# ReboostV2__Vsense.net
KiCad netlist of a schematic drawn in Altium Designer
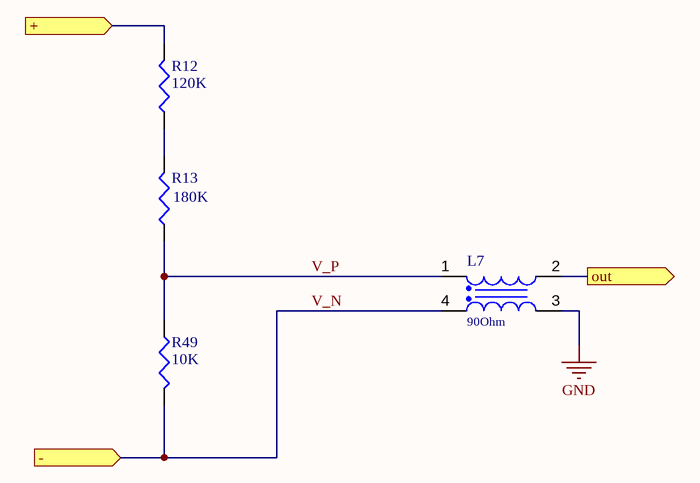
[diagram p0: ReboostV2__Vsense.SchDoc]

(export (version "E")
  (design (tool "Eeschema 10.0.6"))
  (components
    (comp (ref "L7")
      (value "90Ohm")
      (footprint "WE-CNSW_0805")
      (description "WE-CNSW SMT Common Mode Line Filter, size 0805, 90Ohm, 0.37A, 50V")
      (fields
        (field (name "MANUFACTURER PART NUMBER") "744231091")
        (field (name "MANUFACTURER") "Wurth Elektronik")
      )
      (libsource (lib "Reboostv2") (part "744231091"))
    )
    (comp (ref "R12")
      (value "120K")
      (footprint "0603")
      (description "Resistor, 120K, 1%, 0.063W, 50V, 100PPM, 0603")
      (fields
        (field (name "MANUFACTURER") "VISHAY DRALORIC")
        (field (name "MANUFACTURER PART NUMBER") "CRCW0603120KFKEA")
      )
      (libsource (lib "Reboostv2") (part "120K/0603/0063W/50V"))
    )
    (comp (ref "R13")
      (value "180K")
      (footprint "0603")
      (description "Resistor, 180K, 1%, 0.063W, 50V, 100PPM, 0603")
      (fields
        (field (name "MANUFACTURER") "VISHAY DRALORIC")
        (field (name "MANUFACTURER PART NUMBER") "CRCW0603180KFKEA")
      )
      (libsource (lib "Reboostv2") (part "180K/0603/0063W/50V"))
    )
    (comp (ref "R49")
      (value "10K")
      (footprint "0603")
      (description "Resistor, 10K, 1%, 0.063W, 50V, 100PPM, 0603")
      (fields
        (field (name "MANUFACTURER") "VISHAY DRALORIC")
        (field (name "MANUFACTURER PART NUMBER") "CRCW060310K0FKEA")
      )
      (libsource (lib "Reboostv2") (part "10K/0603/0063W/50V"))
    )
  )
  (nets
    (net (code "1") (name "/+") (class "Default")
      (node (ref "R12") (pin "2") (pinfunction "2_2") (pintype "passive"))
    )
    (net (code "2") (name "/V_N") (class "Default")
      (node (ref "L7") (pin "4") (pinfunction "4_4") (pintype "passive"))
      (node (ref "R49") (pin "2") (pinfunction "2_2") (pintype "passive"))
    )
    (net (code "3") (name "/V_P") (class "Default")
      (node (ref "L7") (pin "1") (pinfunction "1_1") (pintype "passive"))
      (node (ref "R13") (pin "1") (pinfunction "1_1") (pintype "passive"))
      (node (ref "R49") (pin "1") (pinfunction "1_1") (pintype "passive"))
    )
    (net (code "4") (name "/out") (class "Default")
      (node (ref "L7") (pin "2") (pinfunction "2_2") (pintype "passive"))
    )
    (net (code "5") (name "GND") (class "Default")
      (node (ref "L7") (pin "3") (pinfunction "3_3") (pintype "passive"))
    )
    (net (code "6") (name "Net-(R12-Pad1)") (class "Default")
      (node (ref "R12") (pin "1") (pinfunction "1_1") (pintype "passive"))
      (node (ref "R13") (pin "2") (pinfunction "2_2") (pintype "passive"))
    )
  )
)
